# M155X.net
KiCad netlist of a schematic drawn in EAGLE
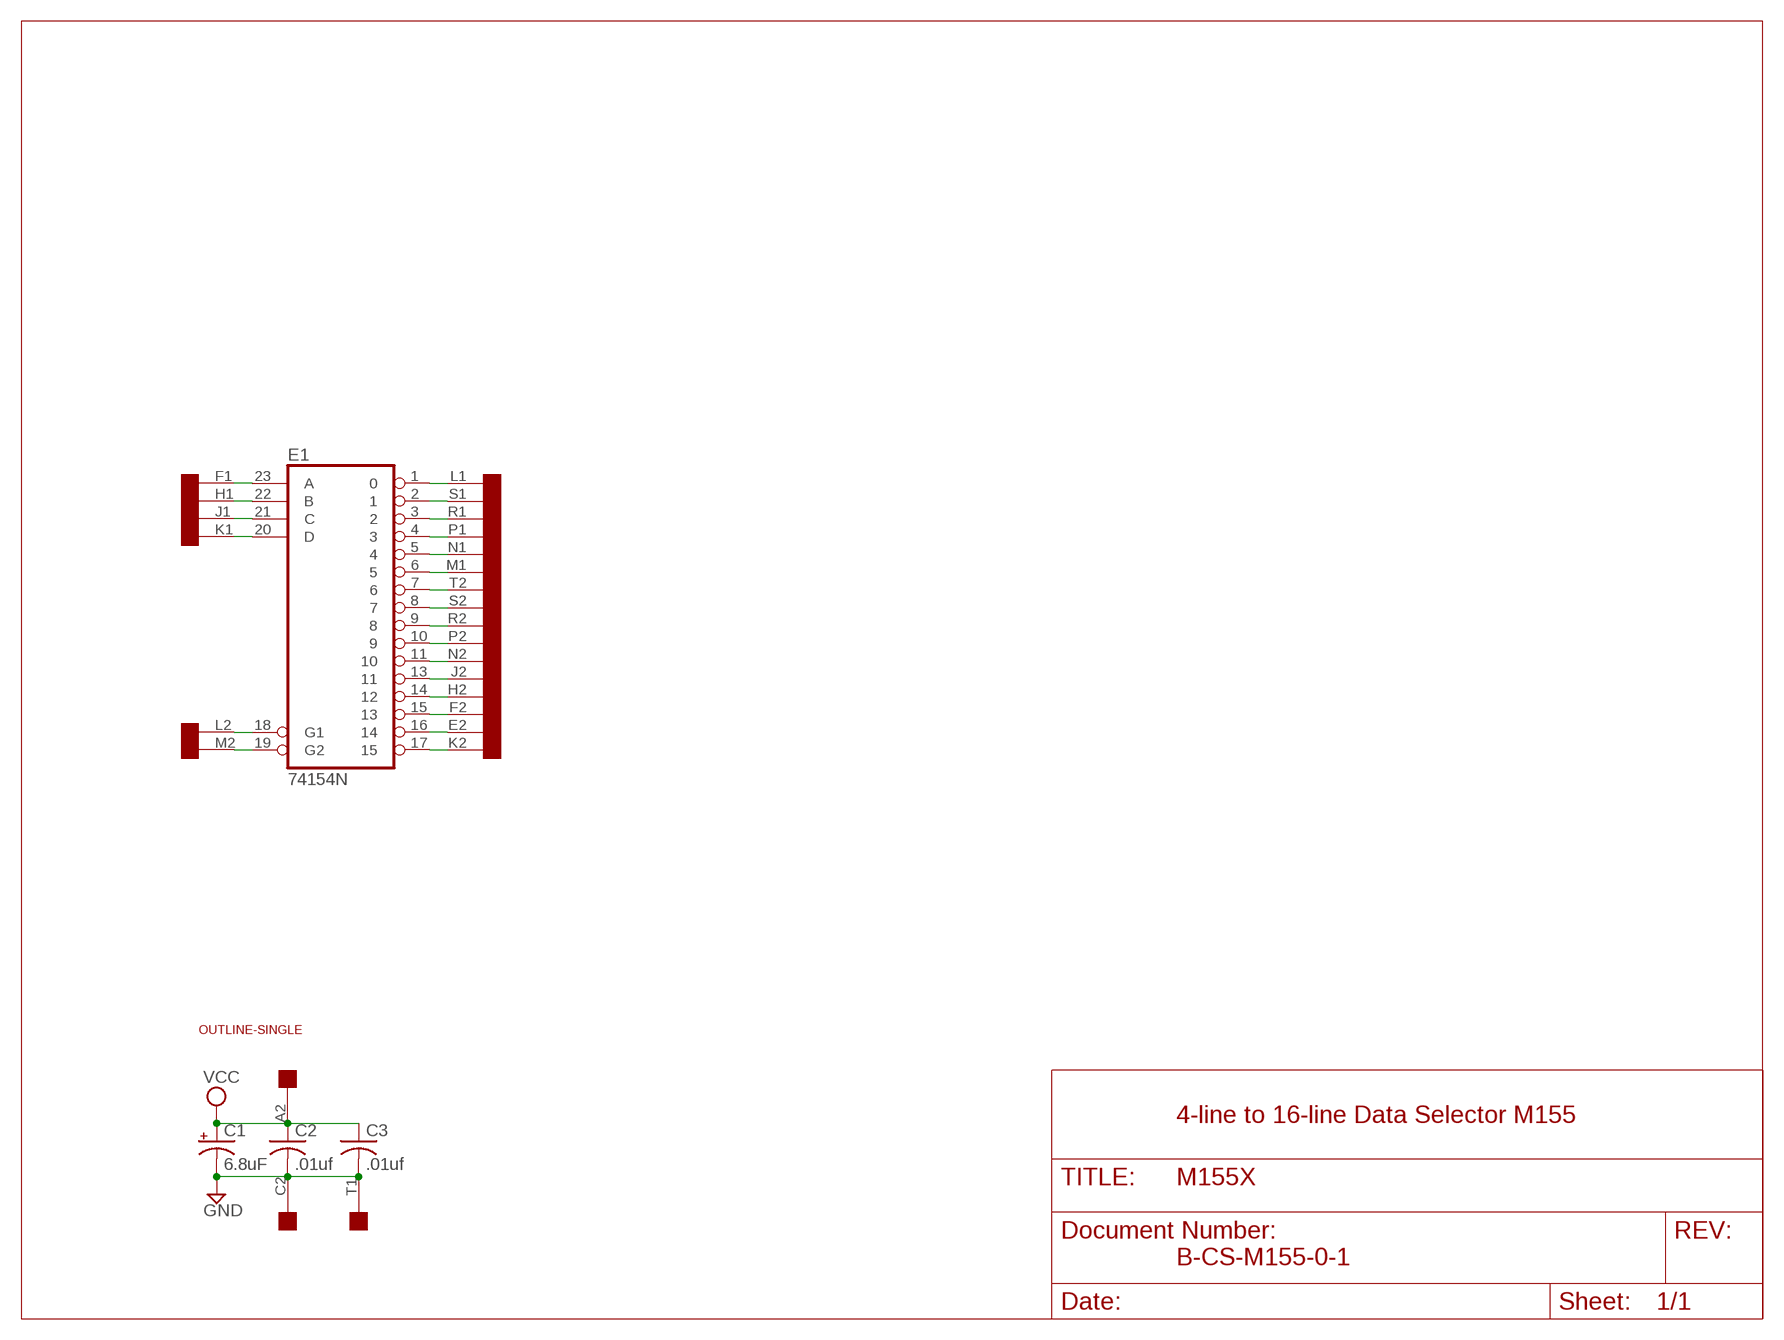
[diagram p0: schematic, sheet 1]

(export (version "E")
  (design (tool "Eeschema 10.0.6"))
  (components
    (comp (ref "C1")
      (value "6.8uF")
      (footprint "eagle-import:E22-6")
      (libsource (lib "eagle-import") (part "CPOL-USE22-6AXIAL"))
    )
    (comp (ref "C2")
      (value ".01uf")
      (footprint "eagle-import:C050-025X075")
      (libsource (lib "eagle-import") (part "C-US050-025X075"))
    )
    (comp (ref "C3")
      (value ".01uf")
      (footprint "eagle-import:C050-025X075")
      (libsource (lib "eagle-import") (part "C-US050-025X075"))
    )
    (comp (ref "E1")
      (value "74154N")
      (footprint "eagle-import:DIL24-6")
      (libsource (lib "eagle-import") (part "74154N"))
    )
    (comp (ref "U$1")
      (value "OUTLINE-SINGLE")
      (footprint "eagle-import:SINGLE")
      (libsource (lib "eagle-import") (part "OUTLINE-SINGLE"))
    )
    (comp (ref "U$2")
      (value "EDGE-2CONNECTOR")
      (footprint "eagle-import:EDGE-CON2")
      (libsource (lib "eagle-import") (part "EDGE-2CONNECTOR"))
    )
  )
  (nets
    (net (code "1") (name "GND") (class "Default")
      (node (ref "C1") (pin "-") (pinfunction "-_-") (pintype "passive"))
      (node (ref "C2") (pin "2") (pinfunction "2_2") (pintype "passive"))
      (node (ref "C3") (pin "2") (pinfunction "2_2") (pintype "passive"))
      (node (ref "U$2") (pin "C2") (pinfunction "1_C2") (pintype "bidirectional"))
      (node (ref "U$2") (pin "T1") (pinfunction "1_T1") (pintype "bidirectional"))
    )
    (net (code "2") (name "Net-(E1A-0)") (class "Default")
      (node (ref "E1") (pin "1") (pinfunction "0_1") (pintype "output"))
      (node (ref "U$2") (pin "L1") (pinfunction "1_L1") (pintype "bidirectional"))
    )
    (net (code "3") (name "Net-(E1A-1)") (class "Default")
      (node (ref "E1") (pin "2") (pinfunction "1_2") (pintype "output"))
      (node (ref "U$2") (pin "S1") (pinfunction "1_S1") (pintype "bidirectional"))
    )
    (net (code "4") (name "Net-(E1A-2)") (class "Default")
      (node (ref "E1") (pin "3") (pinfunction "2_3") (pintype "output"))
      (node (ref "U$2") (pin "R1") (pinfunction "1_R1") (pintype "bidirectional"))
    )
    (net (code "5") (name "Net-(E1A-3)") (class "Default")
      (node (ref "E1") (pin "4") (pinfunction "3_4") (pintype "output"))
      (node (ref "U$2") (pin "P1") (pinfunction "1_P1") (pintype "bidirectional"))
    )
    (net (code "6") (name "Net-(E1A-4)") (class "Default")
      (node (ref "E1") (pin "5") (pinfunction "4_5") (pintype "output"))
      (node (ref "U$2") (pin "N1") (pinfunction "1_N1") (pintype "bidirectional"))
    )
    (net (code "7") (name "Net-(E1A-5)") (class "Default")
      (node (ref "E1") (pin "6") (pinfunction "5_6") (pintype "output"))
      (node (ref "U$2") (pin "M1") (pinfunction "1_M1") (pintype "bidirectional"))
    )
    (net (code "8") (name "Net-(E1A-6)") (class "Default")
      (node (ref "E1") (pin "7") (pinfunction "6_7") (pintype "output"))
      (node (ref "U$2") (pin "T2") (pinfunction "1_T2") (pintype "bidirectional"))
    )
    (net (code "9") (name "Net-(E1A-7)") (class "Default")
      (node (ref "E1") (pin "8") (pinfunction "7_8") (pintype "output"))
      (node (ref "U$2") (pin "S2") (pinfunction "1_S2") (pintype "bidirectional"))
    )
    (net (code "10") (name "Net-(E1A-8)") (class "Default")
      (node (ref "E1") (pin "9") (pinfunction "8_9") (pintype "output"))
      (node (ref "U$2") (pin "R2") (pinfunction "1_R2") (pintype "bidirectional"))
    )
    (net (code "11") (name "Net-(E1A-9)") (class "Default")
      (node (ref "E1") (pin "10") (pinfunction "9_10") (pintype "output"))
      (node (ref "U$2") (pin "P2") (pinfunction "1_P2") (pintype "bidirectional"))
    )
    (net (code "12") (name "Net-(E1A-10)") (class "Default")
      (node (ref "E1") (pin "11") (pinfunction "10_11") (pintype "output"))
      (node (ref "U$2") (pin "N2") (pinfunction "1_N2") (pintype "bidirectional"))
    )
    (net (code "13") (name "Net-(E1A-11)") (class "Default")
      (node (ref "E1") (pin "13") (pinfunction "11_13") (pintype "output"))
      (node (ref "U$2") (pin "J2") (pinfunction "1_J2") (pintype "bidirectional"))
    )
    (net (code "14") (name "Net-(E1A-12)") (class "Default")
      (node (ref "E1") (pin "14") (pinfunction "12_14") (pintype "output"))
      (node (ref "U$2") (pin "H2") (pinfunction "1_H2") (pintype "bidirectional"))
    )
    (net (code "15") (name "Net-(E1A-13)") (class "Default")
      (node (ref "E1") (pin "15") (pinfunction "13_15") (pintype "output"))
      (node (ref "U$2") (pin "F2") (pinfunction "1_F2") (pintype "bidirectional"))
    )
    (net (code "16") (name "Net-(E1A-14)") (class "Default")
      (node (ref "E1") (pin "16") (pinfunction "14_16") (pintype "output"))
      (node (ref "U$2") (pin "E2") (pinfunction "1_E2") (pintype "bidirectional"))
    )
    (net (code "17") (name "Net-(E1A-15)") (class "Default")
      (node (ref "E1") (pin "17") (pinfunction "15_17") (pintype "output"))
      (node (ref "U$2") (pin "K2") (pinfunction "1_K2") (pintype "bidirectional"))
    )
    (net (code "18") (name "Net-(E1A-A)") (class "Default")
      (node (ref "E1") (pin "23") (pinfunction "A_23") (pintype "input"))
      (node (ref "U$2") (pin "F1") (pinfunction "1_F1") (pintype "bidirectional"))
    )
    (net (code "19") (name "Net-(E1A-B)") (class "Default")
      (node (ref "E1") (pin "22") (pinfunction "B_22") (pintype "input"))
      (node (ref "U$2") (pin "H1") (pinfunction "1_H1") (pintype "bidirectional"))
    )
    (net (code "20") (name "Net-(E1A-C)") (class "Default")
      (node (ref "E1") (pin "21") (pinfunction "C_21") (pintype "input"))
      (node (ref "U$2") (pin "J1") (pinfunction "1_J1") (pintype "bidirectional"))
    )
    (net (code "21") (name "Net-(E1A-D)") (class "Default")
      (node (ref "E1") (pin "20") (pinfunction "D_20") (pintype "input"))
      (node (ref "U$2") (pin "K1") (pinfunction "1_K1") (pintype "bidirectional"))
    )
    (net (code "22") (name "Net-(E1A-G1)") (class "Default")
      (node (ref "E1") (pin "18") (pinfunction "G1_18") (pintype "input"))
      (node (ref "U$2") (pin "L2") (pinfunction "1_L2") (pintype "bidirectional"))
    )
    (net (code "23") (name "Net-(E1A-G2)") (class "Default")
      (node (ref "E1") (pin "19") (pinfunction "G2_19") (pintype "input"))
      (node (ref "U$2") (pin "M2") (pinfunction "1_M2") (pintype "bidirectional"))
    )
    (net (code "24") (name "VCC") (class "Default")
      (node (ref "C1") (pin "+") (pinfunction "+_+") (pintype "passive"))
      (node (ref "C2") (pin "1") (pinfunction "1_1") (pintype "passive"))
      (node (ref "C3") (pin "1") (pinfunction "1_1") (pintype "passive"))
      (node (ref "U$2") (pin "A2") (pinfunction "1_A2") (pintype "bidirectional"))
    )
  )
)
